# Metronome.net
KiCad netlist of a schematic drawn in EAGLE
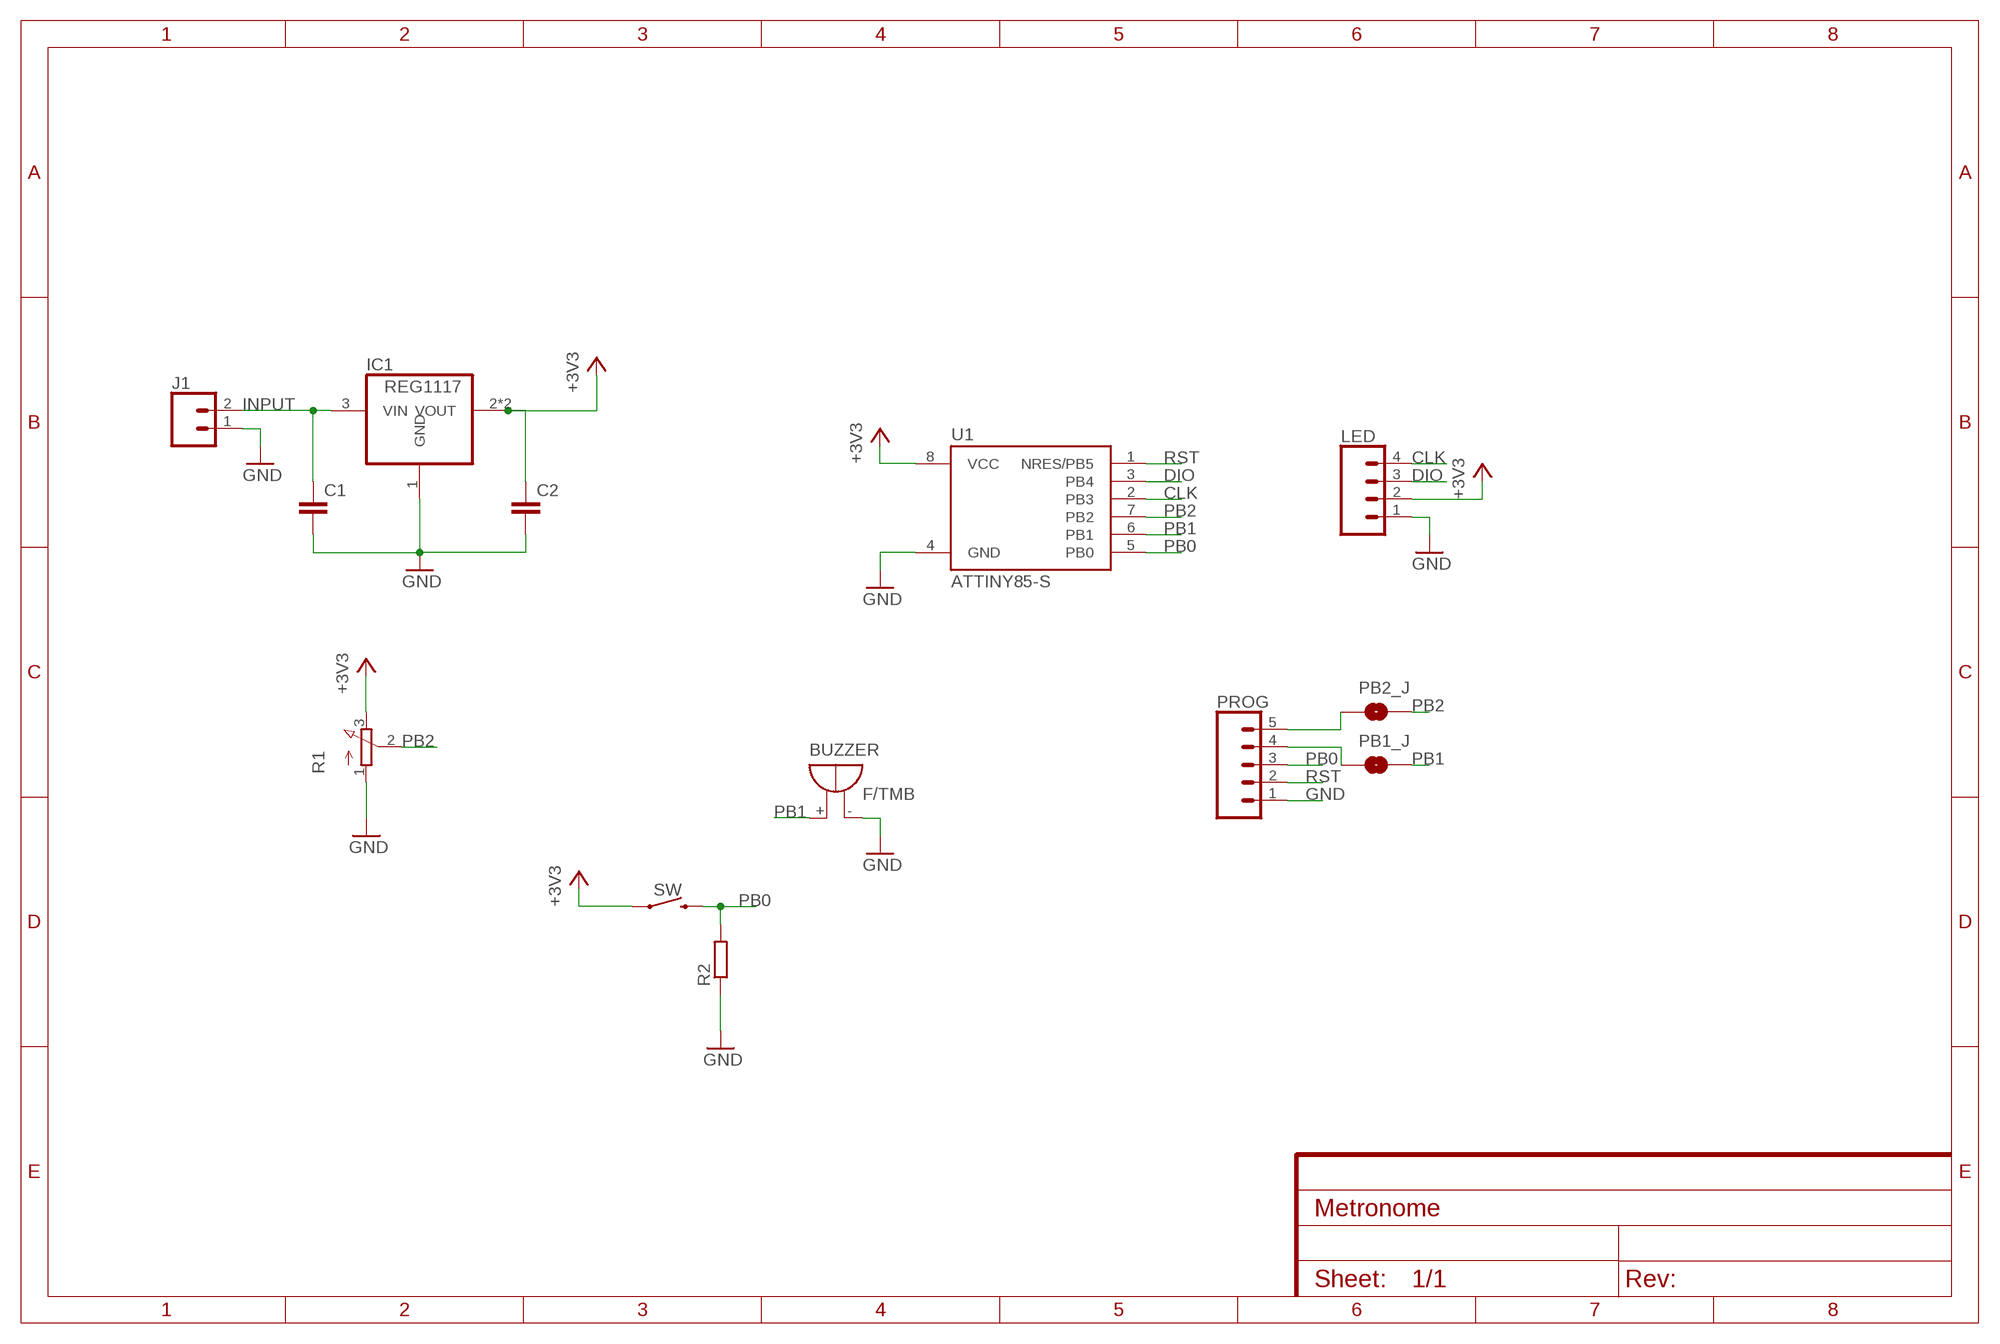
[diagram p0: schematic, sheet 1]

(export (version "E")
  (design (tool "Eeschema 10.0.6"))
  (components
    (comp (ref "BUZZER")
      (value "F/TMB")
      (footprint "eagle-import:F_TMB")
      (libsource (lib "eagle-import") (part "F/TMB"))
    )
    (comp (ref "C1")
      (value "C-EUC1206")
      (footprint "eagle-import:C1206")
      (libsource (lib "eagle-import") (part "C-EUC1206"))
    )
    (comp (ref "C2")
      (value "C-EUC1206")
      (footprint "eagle-import:C1206")
      (libsource (lib "eagle-import") (part "C-EUC1206"))
    )
    (comp (ref "IC1")
      (value "REG1117")
      (footprint "eagle-import:SOT223")
      (libsource (lib "eagle-import") (part "REG1117"))
    )
    (comp (ref "J1")
      (value "CONN_02POLAR")
      (footprint "eagle-import:MOLEX-1X2")
      (libsource (lib "eagle-import") (part "CONN_02POLAR"))
    )
    (comp (ref "LED")
      (value "CONN_04")
      (footprint "eagle-import:1X04")
      (libsource (lib "eagle-import") (part "CONN_04"))
    )
    (comp (ref "PB1_J")
      (value "JUMPER-SMT_2_NO_NO-SILK")
      (footprint "eagle-import:SMT-JUMPER_2_NO_NO-SILK")
      (libsource (lib "eagle-import") (part "JUMPER-SMT_2_NO_NO-SILK"))
    )
    (comp (ref "PB2_J")
      (value "JUMPER-SMT_2_NO_NO-SILK")
      (footprint "eagle-import:SMT-JUMPER_2_NO_NO-SILK")
      (libsource (lib "eagle-import") (part "JUMPER-SMT_2_NO_NO-SILK"))
    )
    (comp (ref "PROG")
      (value "CONN_05")
      (footprint "eagle-import:1X05")
      (libsource (lib "eagle-import") (part "CONN_05"))
    )
    (comp (ref "R1")
      (value "3RP/1610N")
      (footprint "eagle-import:3RP_1610N")
      (libsource (lib "eagle-import") (part "3RP/1610N"))
    )
    (comp (ref "R2")
      (value "R-EU_R1206")
      (footprint "eagle-import:R1206")
      (libsource (lib "eagle-import") (part "R-EU_R1206"))
    )
    (comp (ref "SW")
      (value "MOMENTARY-SWITCH-SPST-PTH-12MM")
      (footprint "eagle-import:TACTILE_SWITCH_PTH_12MM")
      (libsource (lib "eagle-import") (part "MOMENTARY-SWITCH-SPST-PTH-12MM"))
    )
    (comp (ref "U1")
      (value "ATTINY85-S")
      (footprint "eagle-import:SOIC8_EIAJ_208MIL")
      (libsource (lib "eagle-import") (part "ATTINY85S-"))
    )
  )
  (nets
    (net (code "1") (name "+3V3") (class "Default")
      (node (ref "C2") (pin "1") (pinfunction "1_1") (pintype "passive"))
      (node (ref "IC1") (pin "2") (pinfunction "VOUT_2") (pintype "output"))
      (node (ref "IC1") (pin "4") (pinfunction "VOUT_4") (pintype "output"))
      (node (ref "LED") (pin "2") (pinfunction "2_2") (pintype "passive"))
      (node (ref "R1") (pin "3") (pinfunction "E_3") (pintype "passive"))
      (node (ref "SW") (pin "1") (pinfunction "1_1") (pintype "passive"))
      (node (ref "U1") (pin "8") (pinfunction "VCC_8") (pintype "power_in"))
    )
    (net (code "2") (name "/CLK") (class "Default")
      (node (ref "LED") (pin "4") (pinfunction "4_4") (pintype "passive"))
      (node (ref "U1") (pin "2") (pinfunction "PB3_2") (pintype "bidirectional"))
    )
    (net (code "3") (name "/DIO") (class "Default")
      (node (ref "LED") (pin "3") (pinfunction "3_3") (pintype "passive"))
      (node (ref "U1") (pin "3") (pinfunction "PB4_3") (pintype "bidirectional"))
    )
    (net (code "4") (name "/INPUT") (class "Default")
      (node (ref "C1") (pin "1") (pinfunction "1_1") (pintype "passive"))
      (node (ref "IC1") (pin "3") (pinfunction "VIN_3") (pintype "input"))
      (node (ref "J1") (pin "2") (pinfunction "2_2") (pintype "passive"))
    )
    (net (code "5") (name "/PB0") (class "Default")
      (node (ref "PROG") (pin "3") (pinfunction "3_3") (pintype "passive"))
      (node (ref "R2") (pin "2") (pinfunction "2_2") (pintype "passive"))
      (node (ref "SW") (pin "3") (pinfunction "2_3") (pintype "passive"))
      (node (ref "U1") (pin "5") (pinfunction "PB0_5") (pintype "bidirectional"))
    )
    (net (code "6") (name "/PB1") (class "Default")
      (node (ref "BUZZER") (pin "+") (pinfunction "+_+") (pintype "passive"))
      (node (ref "PB1_J") (pin "2") (pinfunction "2_2") (pintype "passive"))
      (node (ref "U1") (pin "6") (pinfunction "PB1_6") (pintype "bidirectional"))
    )
    (net (code "7") (name "/PB2") (class "Default")
      (node (ref "PB2_J") (pin "2") (pinfunction "2_2") (pintype "passive"))
      (node (ref "R1") (pin "2") (pinfunction "S_2") (pintype "passive"))
      (node (ref "U1") (pin "7") (pinfunction "PB2_7") (pintype "bidirectional"))
    )
    (net (code "8") (name "/RST") (class "Default")
      (node (ref "PROG") (pin "2") (pinfunction "2_2") (pintype "passive"))
      (node (ref "U1") (pin "1") (pinfunction "NRES/PB5_1") (pintype "bidirectional"))
    )
    (net (code "9") (name "GND") (class "Default")
      (node (ref "BUZZER") (pin "-") (pinfunction "-_-") (pintype "passive"))
      (node (ref "C1") (pin "2") (pinfunction "2_2") (pintype "passive"))
      (node (ref "C2") (pin "2") (pinfunction "2_2") (pintype "passive"))
      (node (ref "IC1") (pin "1") (pinfunction "GND_1") (pintype "power_in"))
      (node (ref "J1") (pin "1") (pinfunction "1_1") (pintype "passive"))
      (node (ref "LED") (pin "1") (pinfunction "1_1") (pintype "passive"))
      (node (ref "PROG") (pin "1") (pinfunction "1_1") (pintype "passive"))
      (node (ref "R1") (pin "1") (pinfunction "A_1") (pintype "passive"))
      (node (ref "R2") (pin "1") (pinfunction "1_1") (pintype "passive"))
      (node (ref "U1") (pin "4") (pinfunction "GND_4") (pintype "power_in"))
    )
    (net (code "10") (name "Net-(PB1_J-Pad1)") (class "Default")
      (node (ref "PB1_J") (pin "1") (pinfunction "1_1") (pintype "passive"))
      (node (ref "PROG") (pin "4") (pinfunction "4_4") (pintype "passive"))
    )
    (net (code "11") (name "Net-(PB2_J-Pad1)") (class "Default")
      (node (ref "PB2_J") (pin "1") (pinfunction "1_1") (pintype "passive"))
      (node (ref "PROG") (pin "5") (pinfunction "5_5") (pintype "passive"))
    )
  )
)
